# Power.net
KiCad netlist of a schematic drawn in Altium Designer
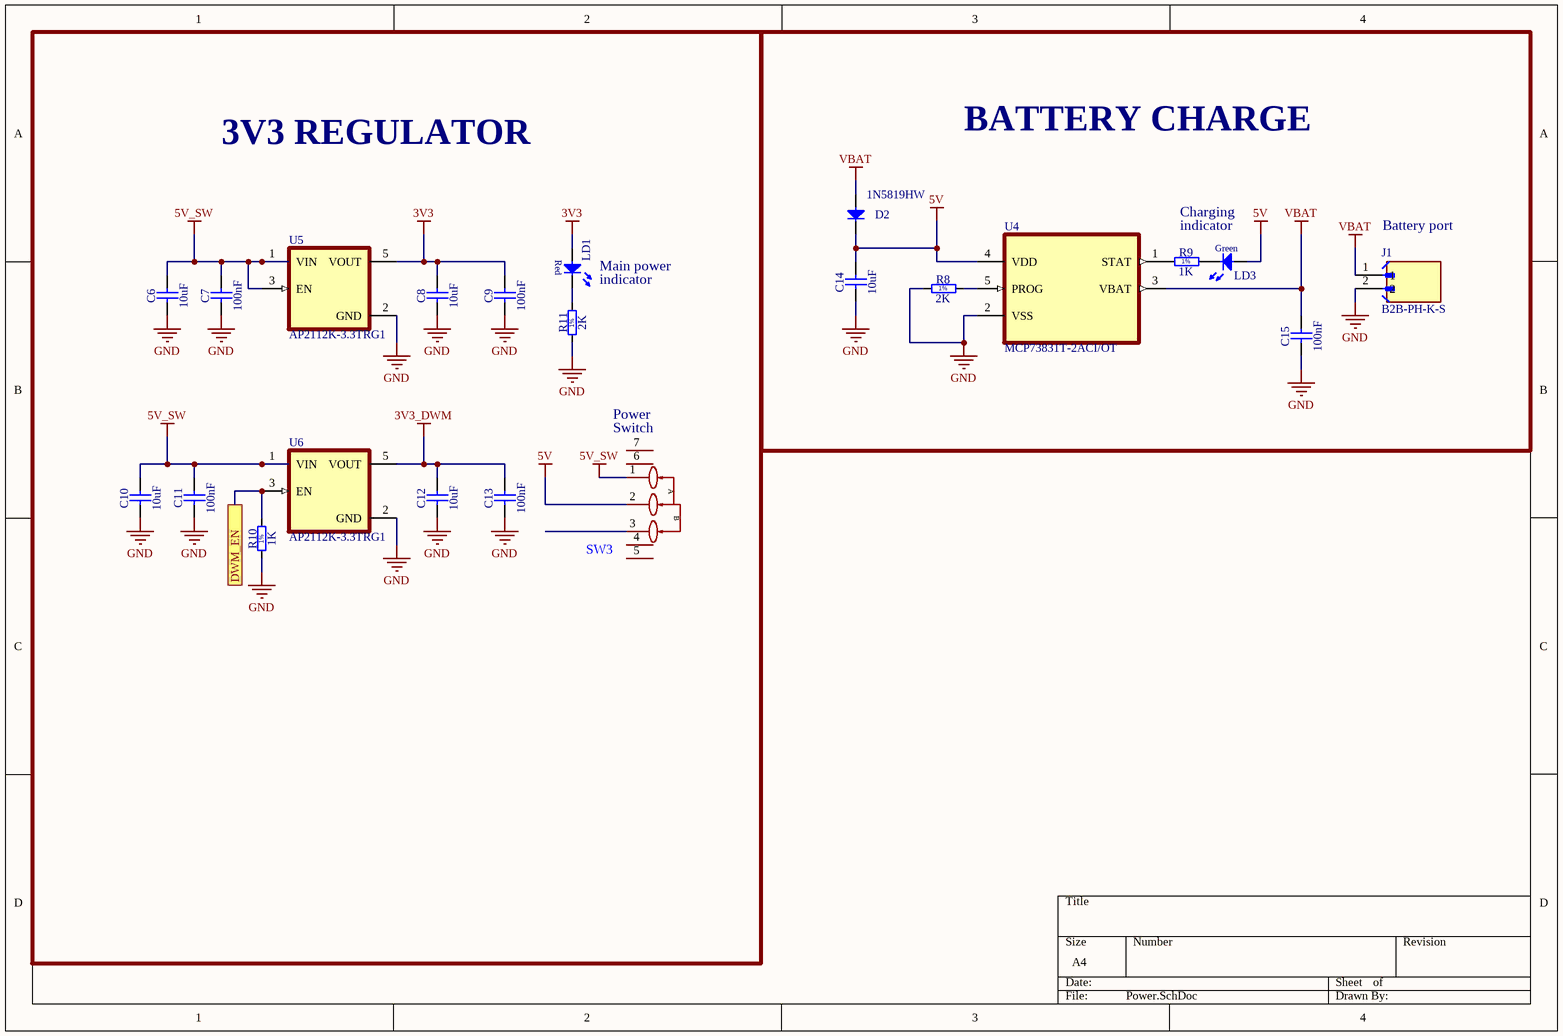
[diagram p0: Power.SchDoc]

(export (version "E")
  (design (tool "Eeschema 10.0.6"))
  (components
    (comp (ref "C6")
      (value "10uF")
      (footprint "0603C")
      (description "Non-polarised capacitor")
      (libsource (lib "Universal Acq") (part "Capacitor - non polarized"))
    )
    (comp (ref "C7")
      (value "100nF")
      (footprint "0603C")
      (description "Non-polarised capacitor")
      (libsource (lib "Universal Acq") (part "Capacitor - non polarized"))
    )
    (comp (ref "C8")
      (value "10uF")
      (footprint "0603C")
      (description "Non-polarised capacitor")
      (libsource (lib "Universal Acq") (part "Capacitor - non polarized"))
    )
    (comp (ref "C9")
      (value "100nF")
      (footprint "0603C")
      (description "Non-polarised capacitor")
      (libsource (lib "Universal Acq") (part "Capacitor - non polarized"))
    )
    (comp (ref "C10")
      (value "10uF")
      (footprint "0603C")
      (description "Non-polarised capacitor")
      (libsource (lib "Universal Acq") (part "Capacitor - non polarized"))
    )
    (comp (ref "C11")
      (value "100nF")
      (footprint "0603C")
      (description "Non-polarised capacitor")
      (libsource (lib "Universal Acq") (part "Capacitor - non polarized"))
    )
    (comp (ref "C12")
      (value "10uF")
      (footprint "0603C")
      (description "Non-polarised capacitor")
      (libsource (lib "Universal Acq") (part "Capacitor - non polarized"))
    )
    (comp (ref "C13")
      (value "100nF")
      (footprint "0603C")
      (description "Non-polarised capacitor")
      (libsource (lib "Universal Acq") (part "Capacitor - non polarized"))
    )
    (comp (ref "C14")
      (value "10uF")
      (footprint "0603C")
      (description "Non-polarised capacitor")
      (libsource (lib "Universal Acq") (part "Capacitor - non polarized"))
    )
    (comp (ref "C15")
      (value "100nF")
      (footprint "0603C")
      (description "Non-polarised capacitor")
      (libsource (lib "Universal Acq") (part "Capacitor - non polarized"))
    )
    (comp (ref "D2")
      (value "1N5819HW")
      (footprint "SOD-123FL")
      (description "Diode Anode Pin 1 Cathode Pin 3 (Pas de pin 2)")
      (libsource (lib "Universal Acq") (part "Diode A1C3"))
    )
    (comp (ref "J1")
      (value "B2B-PH-K-S")
      (footprint "JST_B2B-PH-K-S")
      (description "Connector Header Through Hole 2 position 0.079 (2.00mm)")
      (fields (field (name "MF") "JST Sales America Inc."))
      (libsource (lib "B2B-PH-K-S") (part "B2B-PH-K-S"))
    )
    (comp (ref "LD1")
      (value "~")
      (footprint "0603 LED")
      (description "LED Red 1C 2A")
      (libsource (lib "Universal Acq") (part "LED Red 1C 2A"))
    )
    (comp (ref "LD3")
      (value "GREEN")
      (footprint "0603 LED")
      (description "LED Green 1C 2A")
      (libsource (lib "Universal Acq") (part "LED Green 1C 2A"))
    )
    (comp (ref "R8")
      (value "2K")
      (footprint "0603R")
      (description "Resistor - 1%")
      (libsource (lib "Universal Acq") (part "Resistor - 1%_1"))
    )
    (comp (ref "R9")
      (value "1K")
      (footprint "0603R")
      (description "Resistor - 1%")
      (libsource (lib "Universal Acq") (part "Resistor - 1%_1"))
    )
    (comp (ref "R10")
      (value "1K")
      (footprint "0603R")
      (description "Resistor - 1%")
      (libsource (lib "Universal Acq") (part "Resistor - 1%_1"))
    )
    (comp (ref "R11")
      (value "2K")
      (footprint "0603R")
      (description "Resistor - 1%")
      (libsource (lib "Universal Acq") (part "Resistor - 1%_1"))
    )
    (comp (ref "SW3")
      (value "MK-12C02-G020")
      (footprint "SW-SMD_MK-12C02-G020")
      (fields (field (name "MANUFACTURER") "G-Switch(品赞)"))
      (libsource (lib "MK-12C02-G020") (part "MK-12C02-G020"))
    )
    (comp (ref "U4")
      (value "MCP73831T-2ACI/OT")
      (footprint "SOT95P280X145-5N")
      (description "Charger IC Lithium Ion/Polymer SOT-23-5")
      (fields (field (name "MF") "Microchip"))
      (libsource (lib "MCP73831T-2ACI_OT") (part "MCP73831T-2ACI/OT"))
    )
    (comp (ref "U5")
      (value "AP2112K-3.3TRG1")
      (footprint "SOT95P285X140-5N")
      (description "Linear Voltage Regulator IC Positive Fixed 1 Output 600mA SOT-25")
      (fields (field (name "MF") "Diodes Inc."))
      (libsource (lib "AP2112K-3.3TRG1") (part "AP2112K-3.3TRG1"))
    )
    (comp (ref "U6")
      (value "AP2112K-3.3TRG1")
      (footprint "SOT95P285X140-5N")
      (description "Linear Voltage Regulator IC Positive Fixed 1 Output 600mA SOT-25")
      (fields (field (name "MF") "Diodes Inc."))
      (libsource (lib "AP2112K-3.3TRG1") (part "AP2112K-3.3TRG1"))
    )
  )
  (nets
    (net (code "1") (name "/DWM_EN") (class "Default")
      (node (ref "R10") (pin "2") (pinfunction "2_2") (pintype "passive"))
      (node (ref "U6") (pin "3") (pinfunction "EN_3") (pintype "input"))
    )
    (net (code "2") (name "3V3") (class "Default")
      (node (ref "C8") (pin "2") (pinfunction "2_2") (pintype "passive"))
      (node (ref "C9") (pin "2") (pinfunction "2_2") (pintype "passive"))
      (node (ref "LD1") (pin "2") (pinfunction "A_2") (pintype "passive"))
      (node (ref "U5") (pin "5") (pinfunction "VOUT_5") (pintype "power_in"))
    )
    (net (code "3") (name "3V3_DWM") (class "Default")
      (node (ref "C12") (pin "2") (pinfunction "2_2") (pintype "passive"))
      (node (ref "C13") (pin "2") (pinfunction "2_2") (pintype "passive"))
      (node (ref "U6") (pin "5") (pinfunction "VOUT_5") (pintype "power_in"))
    )
    (net (code "4") (name "5V") (class "Default")
      (node (ref "C14") (pin "2") (pinfunction "2_2") (pintype "passive"))
      (node (ref "D2") (pin "1") (pinfunction "C_1") (pintype "passive"))
      (node (ref "LD3") (pin "2") (pinfunction "A_2") (pintype "passive"))
      (node (ref "SW3") (pin "2") (pinfunction "2_2") (pintype "passive"))
      (node (ref "U4") (pin "4") (pinfunction "VDD_4") (pintype "power_in"))
    )
    (net (code "5") (name "5V_SW") (class "Default")
      (node (ref "C10") (pin "2") (pinfunction "2_2") (pintype "passive"))
      (node (ref "C11") (pin "2") (pinfunction "2_2") (pintype "passive"))
      (node (ref "C6") (pin "2") (pinfunction "2_2") (pintype "passive"))
      (node (ref "C7") (pin "2") (pinfunction "2_2") (pintype "passive"))
      (node (ref "SW3") (pin "1") (pinfunction "1_1") (pintype "passive"))
      (node (ref "U5") (pin "1") (pinfunction "VIN_1") (pintype "power_in"))
      (node (ref "U5") (pin "3") (pinfunction "EN_3") (pintype "input"))
      (node (ref "U6") (pin "1") (pinfunction "VIN_1") (pintype "power_in"))
    )
    (net (code "6") (name "GND") (class "Default")
      (node (ref "C10") (pin "1") (pinfunction "1_1") (pintype "passive"))
      (node (ref "C11") (pin "1") (pinfunction "1_1") (pintype "passive"))
      (node (ref "C12") (pin "1") (pinfunction "1_1") (pintype "passive"))
      (node (ref "C13") (pin "1") (pinfunction "1_1") (pintype "passive"))
      (node (ref "C14") (pin "1") (pinfunction "1_1") (pintype "passive"))
      (node (ref "C15") (pin "1") (pinfunction "1_1") (pintype "passive"))
      (node (ref "C6") (pin "1") (pinfunction "1_1") (pintype "passive"))
      (node (ref "C7") (pin "1") (pinfunction "1_1") (pintype "passive"))
      (node (ref "C8") (pin "1") (pinfunction "1_1") (pintype "passive"))
      (node (ref "C9") (pin "1") (pinfunction "1_1") (pintype "passive"))
      (node (ref "J1") (pin "2") (pinfunction "2_2") (pintype "passive"))
      (node (ref "R10") (pin "1") (pinfunction "1_1") (pintype "passive"))
      (node (ref "R11") (pin "1") (pinfunction "1_1") (pintype "passive"))
      (node (ref "R8") (pin "1") (pinfunction "1_1") (pintype "passive"))
      (node (ref "U4") (pin "2") (pinfunction "VSS_2") (pintype "power_in"))
      (node (ref "U5") (pin "2") (pinfunction "GND_2") (pintype "power_in"))
      (node (ref "U6") (pin "2") (pinfunction "GND_2") (pintype "power_in"))
    )
    (net (code "7") (name "Net-(LD1-C)") (class "Default")
      (node (ref "LD1") (pin "1") (pinfunction "C_1") (pintype "passive"))
      (node (ref "R11") (pin "2") (pinfunction "2_2") (pintype "passive"))
    )
    (net (code "8") (name "Net-(LD3-C)") (class "Default")
      (node (ref "LD3") (pin "1") (pinfunction "C_1") (pintype "passive"))
      (node (ref "R9") (pin "2") (pinfunction "2_2") (pintype "passive"))
    )
    (net (code "9") (name "Net-(U4-PROG)") (class "Default")
      (node (ref "R8") (pin "2") (pinfunction "2_2") (pintype "passive"))
      (node (ref "U4") (pin "5") (pinfunction "PROG_5") (pintype "input"))
    )
    (net (code "10") (name "Net-(U4-STAT)") (class "Default")
      (node (ref "R9") (pin "1") (pinfunction "1_1") (pintype "passive"))
      (node (ref "U4") (pin "1") (pinfunction "STAT_1") (pintype "output"))
    )
    (net (code "11") (name "VBAT") (class "Default")
      (node (ref "C15") (pin "2") (pinfunction "2_2") (pintype "passive"))
      (node (ref "D2") (pin "2") (pinfunction "A_2") (pintype "passive"))
      (node (ref "J1") (pin "1") (pinfunction "1_1") (pintype "passive"))
      (node (ref "U4") (pin "3") (pinfunction "VBAT_3") (pintype "output"))
    )
    (net (code "12") (name "unconnected-(SW3-Pad3)") (class "Default")
      (node (ref "SW3") (pin "3") (pinfunction "3_3") (pintype "passive"))
    )
    (net (code "13") (name "unconnected-(SW3-Pad4)") (class "Default")
      (node (ref "SW3") (pin "4") (pinfunction "4_4") (pintype "passive"))
    )
    (net (code "14") (name "unconnected-(SW3-Pad5)") (class "Default")
      (node (ref "SW3") (pin "5") (pinfunction "5_5") (pintype "passive"))
    )
    (net (code "15") (name "unconnected-(SW3-Pad6)") (class "Default")
      (node (ref "SW3") (pin "6") (pinfunction "6_6") (pintype "passive"))
    )
    (net (code "16") (name "unconnected-(SW3-Pad7)") (class "Default")
      (node (ref "SW3") (pin "7") (pinfunction "7_7") (pintype "passive"))
    )
  )
)
